# GPS.net
KiCad netlist of a schematic drawn in Altium Designer
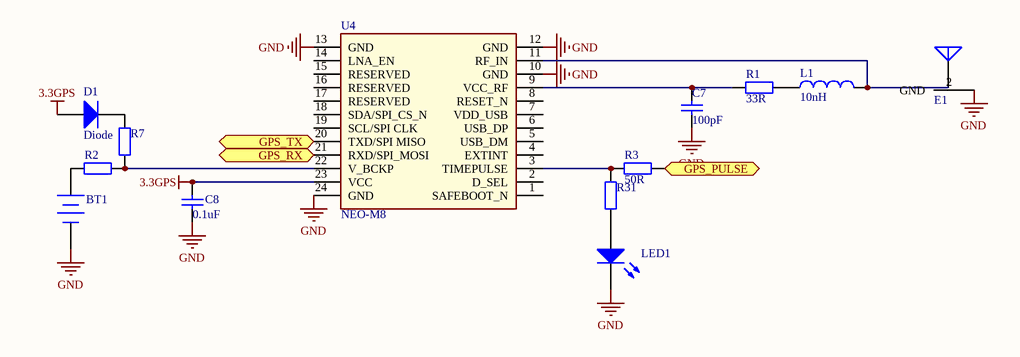
[diagram p0: GPS.SchDoc]

(export (version "E")
  (design (tool "Eeschema 10.0.6"))
  (components
    (comp (ref "BT1")
      (value "Battery")
      (footprint "XH414H-IV01E")
      (description "Multicell Battery")
      (fields (field (name "PUBLISHER") "Altium Limited"))
      (libsource (lib "Miscellaneous Devices") (part "Battery"))
    )
    (comp (ref "C7")
      (value "100pF")
      (footprint "0402")
      (description "Capacitor")
      (fields (field (name "PUBLISHER") "Altium Limited"))
      (libsource (lib "RTC6705") (part "Cap"))
    )
    (comp (ref "C8")
      (value "0.1uF")
      (footprint "0402")
      (description "Capacitor")
      (fields (field (name "PUBLISHER") "Altium Limited"))
      (libsource (lib "RTC6705") (part "Cap"))
    )
    (comp (ref "D1")
      (value "Diode")
      (footprint "LC-SOD-323")
      (description "Default Diode")
      (fields (field (name "PUBLISHER") "Altium Limited"))
      (libsource (lib "Miscellaneous Devices") (part "Diode"))
    )
    (comp (ref "E1")
      (value "Antenna")
      (footprint "IPEX")
      (description "Generic Antenna")
      (fields (field (name "PUBLISHER") "Altium Limited"))
      (libsource (lib "Miscellaneous Devices") (part "Antenna"))
    )
    (comp (ref "L1")
      (value "10nH")
      (footprint "0402")
      (description "Inductor")
      (fields (field (name "PUBLISHER") "Altium Limited"))
      (libsource (lib "Miscellaneous Devices") (part "Inductor"))
    )
    (comp (ref "LED1")
      (value "LED0")
      (footprint "0603")
      (description "Typical INFRARED GaAs LED")
      (fields (field (name "PUBLISHER") "Altium Limited"))
      (libsource (lib "Miscellaneous Devices") (part "LED0"))
    )
    (comp (ref "R1")
      (value "33R")
      (footprint "0402")
      (description "Resistor")
      (fields (field (name "PUBLISHER") "Altium Limited"))
      (libsource (lib "") (part "Res2_1"))
    )
    (comp (ref "R2")
      (value "~")
      (footprint "0402")
      (description "Resistor")
      (fields (field (name "PUBLISHER") "Altium Limited"))
      (libsource (lib "") (part "Res2_1"))
    )
    (comp (ref "R3")
      (value "50R")
      (footprint "0402")
      (description "Resistor")
      (fields (field (name "PUBLISHER") "Altium Limited"))
      (libsource (lib "RTC6705") (part "Res2"))
    )
    (comp (ref "R7")
      (value "~")
      (footprint "0402")
      (description "Resistor")
      (fields (field (name "PUBLISHER") "Altium Limited"))
      (libsource (lib "Miscellaneous Devices") (part "Res2"))
    )
    (comp (ref "R31")
      (value "~")
      (footprint "0402")
      (description "Resistor")
      (fields (field (name "PUBLISHER") "Altium Limited"))
      (libsource (lib "Miscellaneous Devices") (part "Res2"))
    )
    (comp (ref "U4")
      (value "NEO-M8")
      (footprint "NEO")
      (description "u-blox NEO GNSS module")
      (fields (field (name "MANUFACTURER") "u-blox"))
      (libsource (lib "ubloxLib") (part "NEO"))
    )
  )
  (nets
    (net (code "1") (name "/GPS_PULSE") (class "Default")
      (node (ref "R3") (pin "1") (pinfunction "1_1") (pintype "passive"))
    )
    (net (code "2") (name "/GPS_RX") (class "Default")
      (node (ref "U4") (pin "21") (pinfunction "RXD/SPI_MOSI_21") (pintype "passive"))
    )
    (net (code "3") (name "/GPS_TX") (class "Default")
      (node (ref "U4") (pin "20") (pinfunction "TXD/SPI_MISO_20") (pintype "passive"))
    )
    (net (code "4") (name "3.3GPS") (class "Default")
      (node (ref "C8") (pin "2") (pinfunction "2_2") (pintype "passive"))
      (node (ref "D1") (pin "1") (pinfunction "A_1") (pintype "passive"))
      (node (ref "U4") (pin "23") (pinfunction "VCC_23") (pintype "passive"))
    )
    (net (code "5") (name "GND") (class "Default")
      (node (ref "BT1") (pin "2") (pinfunction "-_2") (pintype "passive"))
      (node (ref "C7") (pin "1") (pinfunction "1_1") (pintype "passive"))
      (node (ref "C8") (pin "1") (pinfunction "1_1") (pintype "passive"))
      (node (ref "E1") (pin "2") (pinfunction "GND_2") (pintype "passive"))
      (node (ref "LED1") (pin "2") (pinfunction "K_2") (pintype "passive"))
      (node (ref "U4") (pin "10") (pinfunction "GND_10") (pintype "passive"))
      (node (ref "U4") (pin "12") (pinfunction "GND_12") (pintype "passive"))
      (node (ref "U4") (pin "13") (pinfunction "GND_13") (pintype "passive"))
      (node (ref "U4") (pin "24") (pinfunction "GND_24") (pintype "passive"))
    )
    (net (code "6") (name "Net-(BT1-+)") (class "Default")
      (node (ref "BT1") (pin "1") (pinfunction "+_1") (pintype "passive"))
      (node (ref "R2") (pin "1") (pinfunction "1_1") (pintype "passive"))
    )
    (net (code "7") (name "Net-(D1-K)") (class "Default")
      (node (ref "D1") (pin "2") (pinfunction "K_2") (pintype "passive"))
      (node (ref "R7") (pin "1") (pinfunction "1_1") (pintype "passive"))
    )
    (net (code "8") (name "Net-(E1-ANT)") (class "Default")
      (node (ref "E1") (pin "1") (pinfunction "ANT_1") (pintype "passive"))
      (node (ref "L1") (pin "2") (pinfunction "2_2") (pintype "passive"))
      (node (ref "U4") (pin "11") (pinfunction "RF_IN_11") (pintype "passive"))
    )
    (net (code "9") (name "Net-(L1-Pad1)") (class "Default")
      (node (ref "L1") (pin "1") (pinfunction "1_1") (pintype "passive"))
      (node (ref "R1") (pin "2") (pinfunction "2_2") (pintype "passive"))
    )
    (net (code "10") (name "Net-(LED1-A)") (class "Default")
      (node (ref "LED1") (pin "1") (pinfunction "A_1") (pintype "passive"))
      (node (ref "R31") (pin "2") (pinfunction "2_2") (pintype "passive"))
    )
    (net (code "11") (name "Net-(U4-TIMEPULSE)") (class "Default")
      (node (ref "R3") (pin "2") (pinfunction "2_2") (pintype "passive"))
      (node (ref "R31") (pin "1") (pinfunction "1_1") (pintype "passive"))
      (node (ref "U4") (pin "3") (pinfunction "TIMEPULSE_3") (pintype "passive"))
    )
    (net (code "12") (name "Net-(U4-VCC_RF)") (class "Default")
      (node (ref "C7") (pin "2") (pinfunction "2_2") (pintype "passive"))
      (node (ref "R1") (pin "1") (pinfunction "1_1") (pintype "passive"))
      (node (ref "U4") (pin "9") (pinfunction "VCC_RF_9") (pintype "passive"))
    )
    (net (code "13") (name "Net-(U4-V_BCKP)") (class "Default")
      (node (ref "R2") (pin "2") (pinfunction "2_2") (pintype "passive"))
      (node (ref "R7") (pin "2") (pinfunction "2_2") (pintype "passive"))
      (node (ref "U4") (pin "22") (pinfunction "V_BCKP_22") (pintype "passive"))
    )
    (net (code "14") (name "unconnected-(U4-D_SEL-Pad2)") (class "Default")
      (node (ref "U4") (pin "2") (pinfunction "D_SEL_2") (pintype "passive"))
    )
    (net (code "15") (name "unconnected-(U4-EXTINT-Pad4)") (class "Default")
      (node (ref "U4") (pin "4") (pinfunction "EXTINT_4") (pintype "passive"))
    )
    (net (code "16") (name "unconnected-(U4-LNA_EN-Pad14)") (class "Default")
      (node (ref "U4") (pin "14") (pinfunction "LNA_EN_14") (pintype "passive"))
    )
    (net (code "17") (name "unconnected-(U4-RESERVED-Pad15)") (class "Default")
      (node (ref "U4") (pin "15") (pinfunction "RESERVED_15") (pintype "passive"))
    )
    (net (code "18") (name "unconnected-(U4-RESERVED-Pad16)") (class "Default")
      (node (ref "U4") (pin "16") (pinfunction "RESERVED_16") (pintype "passive"))
    )
    (net (code "19") (name "unconnected-(U4-RESERVED-Pad17)") (class "Default")
      (node (ref "U4") (pin "17") (pinfunction "RESERVED_17") (pintype "passive"))
    )
    (net (code "20") (name "unconnected-(U4-RESET_N-Pad8)") (class "Default")
      (node (ref "U4") (pin "8") (pinfunction "RESET_N_8") (pintype "passive"))
    )
    (net (code "21") (name "unconnected-(U4-SAFEBOOT_N-Pad1)") (class "Default")
      (node (ref "U4") (pin "1") (pinfunction "SAFEBOOT_N_1") (pintype "passive"))
    )
    (net (code "22") (name "unconnected-(U4-SCL{slash}SPI_CLK-Pad19)") (class "Default")
      (node (ref "U4") (pin "19") (pinfunction "SCL/SPI_CLK_19") (pintype "passive"))
    )
    (net (code "23") (name "unconnected-(U4-SDA{slash}SPI_CS_N-Pad18)") (class "Default")
      (node (ref "U4") (pin "18") (pinfunction "SDA/SPI_CS_N_18") (pintype "passive"))
    )
    (net (code "24") (name "unconnected-(U4-USB_DM-Pad5)") (class "Default")
      (node (ref "U4") (pin "5") (pinfunction "USB_DM_5") (pintype "passive"))
    )
    (net (code "25") (name "unconnected-(U4-USB_DP-Pad6)") (class "Default")
      (node (ref "U4") (pin "6") (pinfunction "USB_DP_6") (pintype "passive"))
    )
    (net (code "26") (name "unconnected-(U4-VDD_USB-Pad7)") (class "Default")
      (node (ref "U4") (pin "7") (pinfunction "VDD_USB_7") (pintype "passive"))
    )
  )
)
